# V2_0.net
KiCad netlist of a schematic drawn in Altium Designer
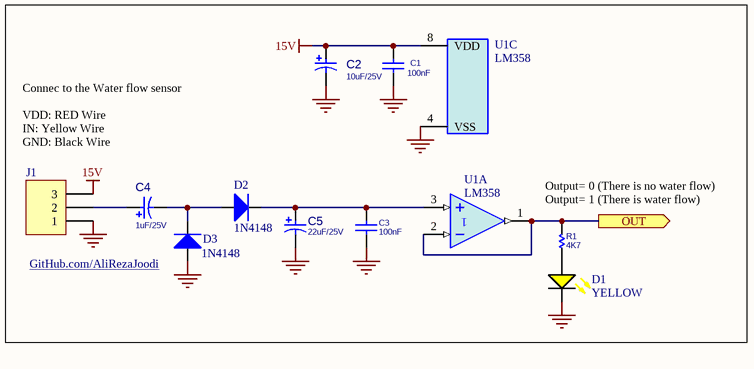
[diagram p0: V2.0.SchDoc]

(export (version "E")
  (design (tool "Eeschema 10.0.6"))
  (components
    (comp (ref "C1")
      (value "100nF")
      (footprint "C_THD_CER_(P2.54-D3.5-T1.5)")
      (description "Capacitor, Ceramic Multilayer")
      (libsource (lib "Passive") (part "Capacitor_Ceramic"))
    )
    (comp (ref "C2")
      (value "10uF/25V")
      (footprint "C_THD_EL_(P2.54-D6-H11)")
      (description "Capacitor, Electrolytic")
      (libsource (lib "Passive") (part "Capacitor_Electrolytic"))
    )
    (comp (ref "C3")
      (value "100nF")
      (footprint "C_THD_CER_(P2.54-D3.5-T1.5)")
      (description "Capacitor, Ceramic Multilayer")
      (libsource (lib "Passive") (part "Capacitor_Ceramic"))
    )
    (comp (ref "C4")
      (value "1uF/25V")
      (footprint "C_THD_EL_(P2.54-D6-H11)")
      (description "Capacitor, Electrolytic")
      (libsource (lib "Passive") (part "Capacitor_Electrolytic"))
    )
    (comp (ref "C5")
      (value "22uF/25V")
      (footprint "C_THD_EL_(P2.54-D6-H11)")
      (description "Capacitor, Electrolytic")
      (libsource (lib "Passive") (part "Capacitor_Electrolytic"))
    )
    (comp (ref "D1")
      (value "YELLOW")
      (footprint "LED_THD_5MM_YELLOW")
      (description "LED, Yellow")
      (fields (field (name "MANUFACTURER") "Generic Components") (field (name "PUBLISHER") "Altium Limited"))
      (libsource (lib "Display") (part "LED_YELLOW"))
    )
    (comp (ref "D2")
      (value "1N4148")
      (footprint "D_THD_AXIAL0.3_DO-35")
      (description "Default Diode")
      (fields (field (name "MANUFACTURER") "Generic Components") (field (name "PUBLISHER") "Altium Limited"))
      (libsource (lib "Miscellaneous Devices") (part "Diode"))
    )
    (comp (ref "D3")
      (value "1N4148")
      (footprint "D_THD_AXIAL0.3_DO-35")
      (description "Default Diode")
      (fields (field (name "MANUFACTURER") "Generic Components") (field (name "PUBLISHER") "Altium Limited"))
      (libsource (lib "Miscellaneous Devices") (part "Diode"))
    )
    (comp (ref "J1")
      (value "3PIN")
      (footprint "Connector_Phoenix_3PIN_MSTB")
      (description "Header, 3-Pin")
      (fields (field (name "MANUFACTURER") "Generic Components") (field (name "PUBLISHER") "Altium Limited"))
      (libsource (lib "Miscellaneous Connectors") (part "Header 3"))
    )
    (comp (ref "R1")
      (value "4K7")
      (footprint "R_THD_AXIAL0.4(1/4W)")
      (description "Resistor,")
      (libsource (lib "Passive") (part "Resistor"))
    )
    (comp (ref "U1")
      (value "LM358")
      (footprint "751-02_L")
      (description "Dual Low-Power Operational Amplifier")
      (fields (field (name "PUBLISHER") "Altium Limited"))
      (libsource (lib "Op-Amp") (part "LM358"))
    )
  )
  (nets
    (net (code "1") (name "/OUT") (class "Default")
      (node (ref "R1") (pin "1") (pinfunction "1_1") (pintype "passive"))
      (node (ref "U1") (pin "1") (pinfunction "OUT_1") (pintype "output"))
      (node (ref "U1") (pin "2") (pinfunction "IN-_2") (pintype "input"))
    )
    (net (code "2") (name "15V") (class "Default")
      (node (ref "C1") (pin "1") (pinfunction "1_1") (pintype "passive"))
      (node (ref "C2") (pin "1") (pinfunction "1_1") (pintype "passive"))
      (node (ref "J1") (pin "3") (pinfunction "3_3") (pintype "passive"))
      (node (ref "U1") (pin "8") (pinfunction "VDD_8") (pintype "passive"))
    )
    (net (code "3") (name "GND") (class "Default")
      (node (ref "C1") (pin "2") (pinfunction "2_2") (pintype "passive"))
      (node (ref "C2") (pin "2") (pinfunction "2_2") (pintype "passive"))
      (node (ref "C3") (pin "2") (pinfunction "2_2") (pintype "passive"))
      (node (ref "C5") (pin "2") (pinfunction "2_2") (pintype "passive"))
      (node (ref "D1") (pin "2") (pinfunction "K_2") (pintype "passive"))
      (node (ref "D3") (pin "1") (pinfunction "A_1") (pintype "passive"))
      (node (ref "J1") (pin "1") (pinfunction "1_1") (pintype "passive"))
      (node (ref "U1") (pin "4") (pinfunction "VSS_4") (pintype "power_in"))
    )
    (net (code "4") (name "Net-(C4-Pad1)") (class "Default")
      (node (ref "C4") (pin "1") (pinfunction "1_1") (pintype "passive"))
      (node (ref "J1") (pin "2") (pinfunction "2_2") (pintype "passive"))
    )
    (net (code "5") (name "Net-(D1-A)") (class "Default")
      (node (ref "D1") (pin "1") (pinfunction "A_1") (pintype "passive"))
      (node (ref "R1") (pin "2") (pinfunction "2_2") (pintype "passive"))
    )
    (net (code "6") (name "Net-(D2-A)") (class "Default")
      (node (ref "C4") (pin "2") (pinfunction "2_2") (pintype "passive"))
      (node (ref "D2") (pin "1") (pinfunction "A_1") (pintype "passive"))
      (node (ref "D3") (pin "2") (pinfunction "K_2") (pintype "passive"))
    )
    (net (code "7") (name "Net-(D2-K)") (class "Default")
      (node (ref "C3") (pin "1") (pinfunction "1_1") (pintype "passive"))
      (node (ref "C5") (pin "1") (pinfunction "1_1") (pintype "passive"))
      (node (ref "D2") (pin "2") (pinfunction "K_2") (pintype "passive"))
      (node (ref "U1") (pin "3") (pinfunction "IN+_3") (pintype "input"))
    )
  )
)
